# Power_Isolation.net
KiCad netlist of a schematic drawn in Altium Designer
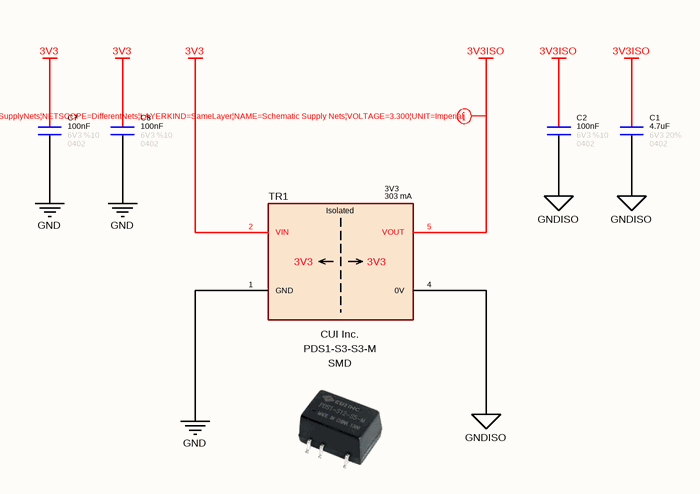
[diagram p0: Power Isolation.SchDoc]

(export (version "E")
  (design (tool "Eeschema 10.0.6"))
  (components
    (comp (ref "C1")
      (value "4.7uF")
      (footprint "CAPACITOR_0402")
      (description "Multilayer Ceramic Capacitors - SMD - 6V3 4.7uF X5R 0402 20%")
      (fields
        (field (name "MANUFACTURER PART NUMBER") "C0402C475M9PACTU")
        (field (name "TOLERANCE") "20%")
        (field (name "CASE") "0402")
        (field (name "VOLTAGE") "6V3")
        (field (name "Comment") "Capacitor - 4.7uF [0402] (Ceramic)")
      )
      (libsource (lib "Akkoyun") (part "Capacitor - 4.7uF [0402-6V3]"))
    )
    (comp (ref "C2")
      (value "100nF")
      (footprint "CAPACITOR_0402")
      (description "Capacitor - 100nF [0402-6V3] (Ceramic)")
      (fields
        (field (name "MANUFACTURER PART NUMBER") "04026D104KAT4A")
        (field (name "TOLERANCE") "%10")
        (field (name "VOLTAGE") "6V3")
        (field (name "CASE") "0402")
        (field (name "Comment") "Capacitor - 100nF [0402] (Ceramic)")
      )
      (libsource (lib "Akkoyun") (part "Capacitor - 100nF [0402-6V3]"))
    )
    (comp (ref "C7")
      (value "100nF")
      (footprint "CAPACITOR_0402")
      (description "Capacitor - 100nF [0402-6V3] (Ceramic)")
      (fields
        (field (name "MANUFACTURER PART NUMBER") "04026D104KAT4A")
        (field (name "TOLERANCE") "%10")
        (field (name "VOLTAGE") "6V3")
        (field (name "CASE") "0402")
        (field (name "Comment") "Capacitor - 100nF [0402] (Ceramic)")
      )
      (libsource (lib "Akkoyun") (part "Capacitor - 100nF [0402-6V3]"))
    )
    (comp (ref "C8")
      (value "100nF")
      (footprint "CAPACITOR_0402")
      (description "Capacitor - 100nF [0402-6V3] (Ceramic)")
      (fields
        (field (name "MANUFACTURER PART NUMBER") "04026D104KAT4A")
        (field (name "TOLERANCE") "%10")
        (field (name "VOLTAGE") "6V3")
        (field (name "CASE") "0402")
        (field (name "Comment") "Capacitor - 100nF [0402] (Ceramic)")
      )
      (libsource (lib "Akkoyun") (part "Capacitor - 100nF [0402-6V3]"))
    )
    (comp (ref "TR1")
      (value "PDS1-S3-S3-M")
      (footprint "PDS1-Sx-Sx-M")
      (description "Module DC-DC 3.3VIN 1-OUT 3.3V 0.303A 1W 5-Pin SMD Module")
      (fields
        (field (name "OUTPUT CURRENT") "303 mA")
        (field (name "OUTPUT VOLTAGE") "3V3")
        (field (name "MANUFACTURER NAME") "CUI Inc.")
        (field (name "MANUFACTURER PART NUMBER") "PDS1-S3-S3-M")
        (field (name "CASE") "SMD")
      )
      (libsource (lib "Akkoyun") (part "Transformator - PDS1-Sx-Sx-M"))
    )
  )
  (nets
    (net (code "1") (name "3V3") (class "Default")
      (node (ref "C7") (pin "2") (pinfunction "2_2") (pintype "passive"))
      (node (ref "C8") (pin "2") (pinfunction "2_2") (pintype "passive"))
      (node (ref "TR1") (pin "2") (pinfunction "VIN_2") (pintype "power_in"))
    )
    (net (code "2") (name "3V3ISO") (class "Default")
      (node (ref "C1") (pin "2") (pinfunction "2_2") (pintype "passive"))
      (node (ref "C2") (pin "2") (pinfunction "2_2") (pintype "passive"))
      (node (ref "TR1") (pin "5") (pinfunction "VOUT_5") (pintype "power_in"))
    )
    (net (code "3") (name "GND") (class "Default")
      (node (ref "C7") (pin "1") (pinfunction "1_1") (pintype "passive"))
      (node (ref "C8") (pin "1") (pinfunction "1_1") (pintype "passive"))
      (node (ref "TR1") (pin "1") (pinfunction "GND_1") (pintype "power_in"))
    )
    (net (code "4") (name "GNDISO") (class "Default")
      (node (ref "C1") (pin "1") (pinfunction "1_1") (pintype "passive"))
      (node (ref "C2") (pin "1") (pinfunction "1_1") (pintype "passive"))
      (node (ref "TR1") (pin "4") (pinfunction "0V_4") (pintype "power_in"))
    )
    (net (code "5") (name "unconnected-(TR1-Terminator-Pad8)") (class "Default")
      (node (ref "TR1") (pin "8") (pinfunction "Terminator_8") (pintype "passive"))
    )
  )
)
